# tunable_filter.net
KiCad netlist of a schematic drawn in EAGLE
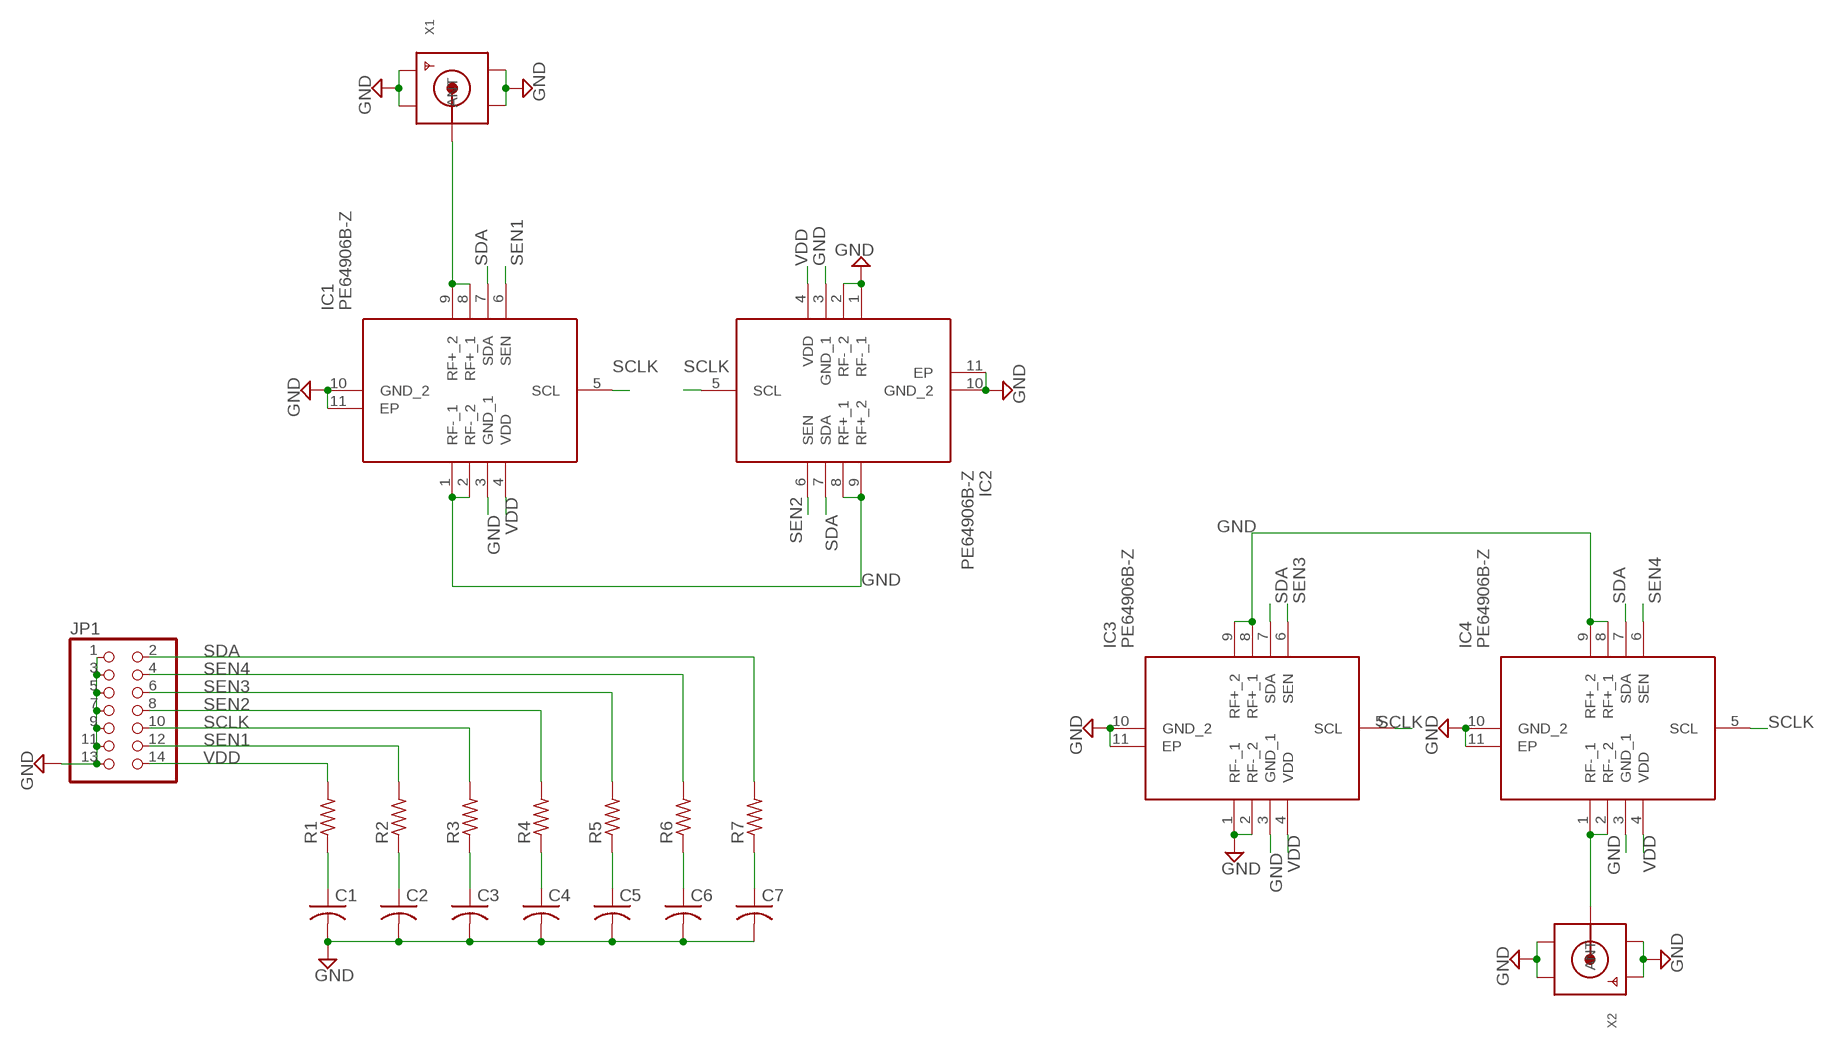
[diagram p0: schematic, sheet 1]

(export (version "E")
  (design (tool "Eeschema 10.0.6"))
  (components
    (comp (ref "C1")
      (value "C-USC0402K")
      (footprint "eagle-import:C0402K")
      (libsource (lib "eagle-import") (part "C-USC0402K"))
    )
    (comp (ref "C2")
      (value "C-USC0402K")
      (footprint "eagle-import:C0402K")
      (libsource (lib "eagle-import") (part "C-USC0402K"))
    )
    (comp (ref "C3")
      (value "C-USC0402K")
      (footprint "eagle-import:C0402K")
      (libsource (lib "eagle-import") (part "C-USC0402K"))
    )
    (comp (ref "C4")
      (value "C-USC0402K")
      (footprint "eagle-import:C0402K")
      (libsource (lib "eagle-import") (part "C-USC0402K"))
    )
    (comp (ref "C5")
      (value "C-USC0402K")
      (footprint "eagle-import:C0402K")
      (libsource (lib "eagle-import") (part "C-USC0402K"))
    )
    (comp (ref "C6")
      (value "C-USC0402K")
      (footprint "eagle-import:C0402K")
      (libsource (lib "eagle-import") (part "C-USC0402K"))
    )
    (comp (ref "C7")
      (value "C-USC0402K")
      (footprint "eagle-import:C0402K")
      (libsource (lib "eagle-import") (part "C-USC0402K"))
    )
    (comp (ref "IC1")
      (value "PE64906B-Z")
      (footprint "eagle-import:QFN50P200X200X60-11N")
      (fields (field (name "MOUSER_PART_NUMBER") "81-PE64906B-Z"))
      (libsource (lib "eagle-import") (part "PE64906B-Z"))
    )
    (comp (ref "IC2")
      (value "PE64906B-Z")
      (footprint "eagle-import:QFN50P200X200X60-11N")
      (fields (field (name "MOUSER_PART_NUMBER") "81-PE64906B-Z"))
      (libsource (lib "eagle-import") (part "PE64906B-Z"))
    )
    (comp (ref "IC3")
      (value "PE64906B-Z")
      (footprint "eagle-import:QFN50P200X200X60-11N")
      (fields (field (name "MOUSER_PART_NUMBER") "81-PE64906B-Z"))
      (libsource (lib "eagle-import") (part "PE64906B-Z"))
    )
    (comp (ref "IC4")
      (value "PE64906B-Z")
      (footprint "eagle-import:QFN50P200X200X60-11N")
      (fields (field (name "MOUSER_PART_NUMBER") "81-PE64906B-Z"))
      (libsource (lib "eagle-import") (part "PE64906B-Z"))
    )
    (comp (ref "JP1")
      (value "PINHD-2X7")
      (footprint "eagle-import:2X07")
      (libsource (lib "eagle-import") (part "PINHD-2X7"))
    )
    (comp (ref "R1")
      (value "R-US_R0402")
      (footprint "eagle-import:R0402")
      (libsource (lib "eagle-import") (part "R-US_R0402"))
    )
    (comp (ref "R2")
      (value "R-US_R0402")
      (footprint "eagle-import:R0402")
      (libsource (lib "eagle-import") (part "R-US_R0402"))
    )
    (comp (ref "R3")
      (value "R-US_R0402")
      (footprint "eagle-import:R0402")
      (libsource (lib "eagle-import") (part "R-US_R0402"))
    )
    (comp (ref "R4")
      (value "R-US_R0402")
      (footprint "eagle-import:R0402")
      (libsource (lib "eagle-import") (part "R-US_R0402"))
    )
    (comp (ref "R5")
      (value "R-US_R0402")
      (footprint "eagle-import:R0402")
      (libsource (lib "eagle-import") (part "R-US_R0402"))
    )
    (comp (ref "R6")
      (value "R-US_R0402")
      (footprint "eagle-import:R0402")
      (libsource (lib "eagle-import") (part "R-US_R0402"))
    )
    (comp (ref "R7")
      (value "R-US_R0402")
      (footprint "eagle-import:R0402")
      (libsource (lib "eagle-import") (part "R-US_R0402"))
    )
    (comp (ref "X1")
      (value "SMACONNECTOR_EDGE")
      (footprint "eagle-import:SMA_EDGELAUNCH")
      (libsource (lib "eagle-import") (part "SMACONNECTOR_EDGE"))
    )
    (comp (ref "X2")
      (value "SMACONNECTOR_EDGE")
      (footprint "eagle-import:SMA_EDGELAUNCH")
      (libsource (lib "eagle-import") (part "SMACONNECTOR_EDGE"))
    )
  )
  (nets
    (net (code "1") (name "/SCLK") (class "Default")
      (node (ref "IC1") (pin "5") (pinfunction "SCL_5") (pintype "bidirectional"))
      (node (ref "IC2") (pin "5") (pinfunction "SCL_5") (pintype "bidirectional"))
      (node (ref "IC3") (pin "5") (pinfunction "SCL_5") (pintype "bidirectional"))
      (node (ref "IC4") (pin "5") (pinfunction "SCL_5") (pintype "bidirectional"))
      (node (ref "JP1") (pin "10") (pinfunction "10_10") (pintype "passive"))
      (node (ref "R3") (pin "2") (pinfunction "2_2") (pintype "passive"))
    )
    (net (code "2") (name "/SDA") (class "Default")
      (node (ref "IC1") (pin "7") (pinfunction "SDA_7") (pintype "bidirectional"))
      (node (ref "IC2") (pin "7") (pinfunction "SDA_7") (pintype "bidirectional"))
      (node (ref "IC3") (pin "7") (pinfunction "SDA_7") (pintype "bidirectional"))
      (node (ref "IC4") (pin "7") (pinfunction "SDA_7") (pintype "bidirectional"))
      (node (ref "JP1") (pin "2") (pinfunction "2_2") (pintype "passive"))
      (node (ref "R7") (pin "2") (pinfunction "2_2") (pintype "passive"))
    )
    (net (code "3") (name "/SEN1") (class "Default")
      (node (ref "IC1") (pin "6") (pinfunction "SEN_6") (pintype "bidirectional"))
      (node (ref "JP1") (pin "12") (pinfunction "12_12") (pintype "passive"))
      (node (ref "R2") (pin "2") (pinfunction "2_2") (pintype "passive"))
    )
    (net (code "4") (name "/SEN2") (class "Default")
      (node (ref "IC2") (pin "6") (pinfunction "SEN_6") (pintype "bidirectional"))
      (node (ref "JP1") (pin "8") (pinfunction "8_8") (pintype "passive"))
      (node (ref "R4") (pin "2") (pinfunction "2_2") (pintype "passive"))
    )
    (net (code "5") (name "/SEN3") (class "Default")
      (node (ref "IC3") (pin "6") (pinfunction "SEN_6") (pintype "bidirectional"))
      (node (ref "JP1") (pin "6") (pinfunction "6_6") (pintype "passive"))
      (node (ref "R5") (pin "2") (pinfunction "2_2") (pintype "passive"))
    )
    (net (code "6") (name "/SEN4") (class "Default")
      (node (ref "IC4") (pin "6") (pinfunction "SEN_6") (pintype "bidirectional"))
      (node (ref "JP1") (pin "4") (pinfunction "4_4") (pintype "passive"))
      (node (ref "R6") (pin "2") (pinfunction "2_2") (pintype "passive"))
    )
    (net (code "7") (name "/VDD") (class "Default")
      (node (ref "IC1") (pin "4") (pinfunction "VDD_4") (pintype "bidirectional"))
      (node (ref "IC2") (pin "4") (pinfunction "VDD_4") (pintype "bidirectional"))
      (node (ref "IC3") (pin "4") (pinfunction "VDD_4") (pintype "bidirectional"))
      (node (ref "IC4") (pin "4") (pinfunction "VDD_4") (pintype "bidirectional"))
      (node (ref "JP1") (pin "14") (pinfunction "14_14") (pintype "passive"))
      (node (ref "R1") (pin "2") (pinfunction "2_2") (pintype "passive"))
    )
    (net (code "8") (name "GND") (class "Default")
      (node (ref "C1") (pin "2") (pinfunction "2_2") (pintype "passive"))
      (node (ref "C2") (pin "2") (pinfunction "2_2") (pintype "passive"))
      (node (ref "C3") (pin "2") (pinfunction "2_2") (pintype "passive"))
      (node (ref "C4") (pin "2") (pinfunction "2_2") (pintype "passive"))
      (node (ref "C5") (pin "2") (pinfunction "2_2") (pintype "passive"))
      (node (ref "C6") (pin "2") (pinfunction "2_2") (pintype "passive"))
      (node (ref "C7") (pin "2") (pinfunction "2_2") (pintype "passive"))
      (node (ref "IC1") (pin "1") (pinfunction "RF-_1_1") (pintype "bidirectional"))
      (node (ref "IC1") (pin "10") (pinfunction "GND_2_10") (pintype "bidirectional"))
      (node (ref "IC1") (pin "11") (pinfunction "EP_11") (pintype "bidirectional"))
      (node (ref "IC1") (pin "2") (pinfunction "RF-_2_2") (pintype "bidirectional"))
      (node (ref "IC1") (pin "3") (pinfunction "GND_1_3") (pintype "bidirectional"))
      (node (ref "IC2") (pin "1") (pinfunction "RF-_1_1") (pintype "bidirectional"))
      (node (ref "IC2") (pin "10") (pinfunction "GND_2_10") (pintype "bidirectional"))
      (node (ref "IC2") (pin "11") (pinfunction "EP_11") (pintype "bidirectional"))
      (node (ref "IC2") (pin "2") (pinfunction "RF-_2_2") (pintype "bidirectional"))
      (node (ref "IC2") (pin "3") (pinfunction "GND_1_3") (pintype "bidirectional"))
      (node (ref "IC2") (pin "8") (pinfunction "RF+_1_8") (pintype "bidirectional"))
      (node (ref "IC2") (pin "9") (pinfunction "RF+_2_9") (pintype "bidirectional"))
      (node (ref "IC3") (pin "1") (pinfunction "RF-_1_1") (pintype "bidirectional"))
      (node (ref "IC3") (pin "10") (pinfunction "GND_2_10") (pintype "bidirectional"))
      (node (ref "IC3") (pin "11") (pinfunction "EP_11") (pintype "bidirectional"))
      (node (ref "IC3") (pin "2") (pinfunction "RF-_2_2") (pintype "bidirectional"))
      (node (ref "IC3") (pin "3") (pinfunction "GND_1_3") (pintype "bidirectional"))
      (node (ref "IC3") (pin "8") (pinfunction "RF+_1_8") (pintype "bidirectional"))
      (node (ref "IC3") (pin "9") (pinfunction "RF+_2_9") (pintype "bidirectional"))
      (node (ref "IC4") (pin "10") (pinfunction "GND_2_10") (pintype "bidirectional"))
      (node (ref "IC4") (pin "11") (pinfunction "EP_11") (pintype "bidirectional"))
      (node (ref "IC4") (pin "3") (pinfunction "GND_1_3") (pintype "bidirectional"))
      (node (ref "IC4") (pin "8") (pinfunction "RF+_1_8") (pintype "bidirectional"))
      (node (ref "IC4") (pin "9") (pinfunction "RF+_2_9") (pintype "bidirectional"))
      (node (ref "JP1") (pin "1") (pinfunction "1_1") (pintype "passive"))
      (node (ref "JP1") (pin "11") (pinfunction "11_11") (pintype "passive"))
      (node (ref "JP1") (pin "13") (pinfunction "13_13") (pintype "passive"))
      (node (ref "JP1") (pin "3") (pinfunction "3_3") (pintype "passive"))
      (node (ref "JP1") (pin "5") (pinfunction "5_5") (pintype "passive"))
      (node (ref "JP1") (pin "7") (pinfunction "7_7") (pintype "passive"))
      (node (ref "JP1") (pin "9") (pinfunction "9_9") (pintype "passive"))
      (node (ref "X1") (pin "GND@1") (pinfunction "GND4_GND@1") (pintype "power_in"))
      (node (ref "X1") (pin "GND@2") (pinfunction "GND3_GND@2") (pintype "power_in"))
      (node (ref "X1") (pin "GND@3") (pinfunction "GND2_GND@3") (pintype "power_in"))
      (node (ref "X1") (pin "GND@4") (pinfunction "GND1_GND@4") (pintype "power_in"))
      (node (ref "X2") (pin "GND@1") (pinfunction "GND4_GND@1") (pintype "power_in"))
      (node (ref "X2") (pin "GND@2") (pinfunction "GND3_GND@2") (pintype "power_in"))
      (node (ref "X2") (pin "GND@3") (pinfunction "GND2_GND@3") (pintype "power_in"))
      (node (ref "X2") (pin "GND@4") (pinfunction "GND1_GND@4") (pintype "power_in"))
    )
    (net (code "9") (name "Net-(C1-Pad1)") (class "Default")
      (node (ref "C1") (pin "1") (pinfunction "1_1") (pintype "passive"))
      (node (ref "R1") (pin "1") (pinfunction "1_1") (pintype "passive"))
    )
    (net (code "10") (name "Net-(C2-Pad1)") (class "Default")
      (node (ref "C2") (pin "1") (pinfunction "1_1") (pintype "passive"))
      (node (ref "R2") (pin "1") (pinfunction "1_1") (pintype "passive"))
    )
    (net (code "11") (name "Net-(C3-Pad1)") (class "Default")
      (node (ref "C3") (pin "1") (pinfunction "1_1") (pintype "passive"))
      (node (ref "R3") (pin "1") (pinfunction "1_1") (pintype "passive"))
    )
    (net (code "12") (name "Net-(C4-Pad1)") (class "Default")
      (node (ref "C4") (pin "1") (pinfunction "1_1") (pintype "passive"))
      (node (ref "R4") (pin "1") (pinfunction "1_1") (pintype "passive"))
    )
    (net (code "13") (name "Net-(C5-Pad1)") (class "Default")
      (node (ref "C5") (pin "1") (pinfunction "1_1") (pintype "passive"))
      (node (ref "R5") (pin "1") (pinfunction "1_1") (pintype "passive"))
    )
    (net (code "14") (name "Net-(C6-Pad1)") (class "Default")
      (node (ref "C6") (pin "1") (pinfunction "1_1") (pintype "passive"))
      (node (ref "R6") (pin "1") (pinfunction "1_1") (pintype "passive"))
    )
    (net (code "15") (name "Net-(C7-Pad1)") (class "Default")
      (node (ref "C7") (pin "1") (pinfunction "1_1") (pintype "passive"))
      (node (ref "R7") (pin "1") (pinfunction "1_1") (pintype "passive"))
    )
    (net (code "16") (name "Net-(IC1-RF+_1)") (class "Default")
      (node (ref "IC1") (pin "8") (pinfunction "RF+_1_8") (pintype "bidirectional"))
      (node (ref "IC1") (pin "9") (pinfunction "RF+_2_9") (pintype "bidirectional"))
      (node (ref "X1") (pin "P") (pinfunction "ANT_P") (pintype "bidirectional"))
    )
    (net (code "17") (name "Net-(IC4-RF-_1)") (class "Default")
      (node (ref "IC4") (pin "1") (pinfunction "RF-_1_1") (pintype "bidirectional"))
      (node (ref "IC4") (pin "2") (pinfunction "RF-_2_2") (pintype "bidirectional"))
      (node (ref "X2") (pin "P") (pinfunction "ANT_P") (pintype "bidirectional"))
    )
  )
)
